# Ethernet.net
KiCad netlist of a schematic drawn in Altium Designer
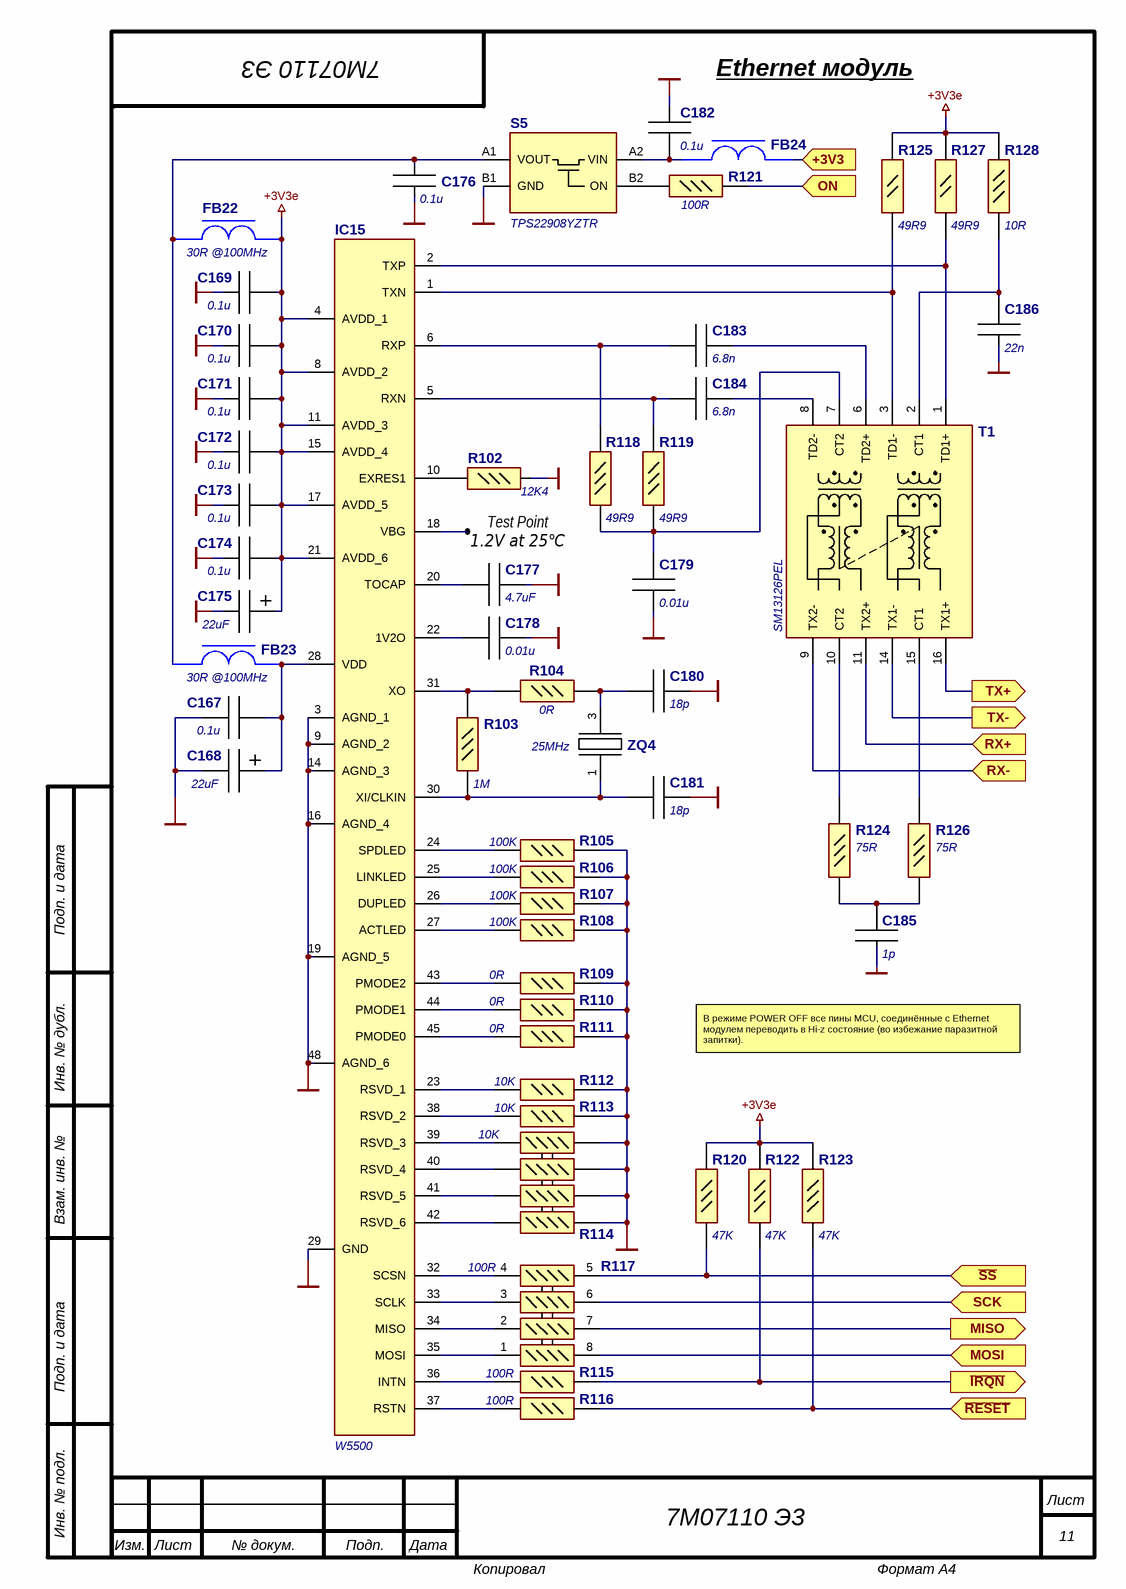
[diagram p0: Ethernet модуль.SchDoc]

(export (version "E")
  (design (tool "Eeschema 10.0.6"))
  (components
    (comp (ref "C167")
      (value "0.1u")
      (footprint ":CAP0402 100x50x50")
      (description "±10% 25V Ceramic Capacitor X7R 0402 (1005 Metric)")
      (fields
        (field (name "MANUFACTURER_PART_NUMBER") "GRM155R71E104KE14J")
        (field (name "MOUSER PART NUMBER") "81-GRM155R71E104KE4J")
      )
      (libsource (lib "Capacitors 0402") (part "GRM155R71E104KE14J"))
    )
    (comp (ref "C168")
      (value "22uF")
      (footprint ":CAP1206 C3216-18")
      (description "22µF Molded Tantalum Capacitors 6.3V 1206 (3216 Metric) 300mOhm @ 100kHz")
      (fields (field (name "MANUFACTURER_PART_NUMBER") "TPSA226K006R0300"))
      (libsource (lib "Capacitors 1206") (part "TPSA226K006R0300"))
    )
    (comp (ref "C169")
      (value "0.1u")
      (footprint ":CAP0402 100x50x50")
      (description "±10% 25V Ceramic Capacitor X7R 0402 (1005 Metric)")
      (fields
        (field (name "MANUFACTURER_PART_NUMBER") "GRM155R71E104KE14J")
        (field (name "MOUSER PART NUMBER") "81-GRM155R71E104KE4J")
      )
      (libsource (lib "Capacitors 0402") (part "GRM155R71E104KE14J"))
    )
    (comp (ref "C170")
      (value "0.1u")
      (footprint ":CAP0402 100x50x50")
      (description "±10% 25V Ceramic Capacitor X7R 0402 (1005 Metric)")
      (fields
        (field (name "MANUFACTURER_PART_NUMBER") "GRM155R71E104KE14J")
        (field (name "MOUSER PART NUMBER") "81-GRM155R71E104KE4J")
      )
      (libsource (lib "Capacitors 0402") (part "GRM155R71E104KE14J"))
    )
    (comp (ref "C171")
      (value "0.1u")
      (footprint ":CAP0402 100x50x50")
      (description "±10% 25V Ceramic Capacitor X7R 0402 (1005 Metric)")
      (fields
        (field (name "MANUFACTURER_PART_NUMBER") "GRM155R71E104KE14J")
        (field (name "MOUSER PART NUMBER") "81-GRM155R71E104KE4J")
      )
      (libsource (lib "Capacitors 0402") (part "GRM155R71E104KE14J"))
    )
    (comp (ref "C172")
      (value "0.1u")
      (footprint ":CAP0402 100x50x50")
      (description "±10% 25V Ceramic Capacitor X7R 0402 (1005 Metric)")
      (fields
        (field (name "MANUFACTURER_PART_NUMBER") "GRM155R71E104KE14J")
        (field (name "MOUSER PART NUMBER") "81-GRM155R71E104KE4J")
      )
      (libsource (lib "Capacitors 0402") (part "GRM155R71E104KE14J"))
    )
    (comp (ref "C173")
      (value "0.1u")
      (footprint ":CAP0402 100x50x50")
      (description "±10% 25V Ceramic Capacitor X7R 0402 (1005 Metric)")
      (fields
        (field (name "MANUFACTURER_PART_NUMBER") "GRM155R71E104KE14J")
        (field (name "MOUSER PART NUMBER") "81-GRM155R71E104KE4J")
      )
      (libsource (lib "Capacitors 0402") (part "GRM155R71E104KE14J"))
    )
    (comp (ref "C174")
      (value "0.1u")
      (footprint ":CAP0402 100x50x50")
      (description "±10% 25V Ceramic Capacitor X7R 0402 (1005 Metric)")
      (fields
        (field (name "MANUFACTURER_PART_NUMBER") "GRM155R71E104KE14J")
        (field (name "MOUSER PART NUMBER") "81-GRM155R71E104KE4J")
      )
      (libsource (lib "Capacitors 0402") (part "GRM155R71E104KE14J"))
    )
    (comp (ref "C175")
      (value "22uF")
      (footprint ":CAP1206 C3216-18")
      (description "22µF Molded Tantalum Capacitors 6.3V 1206 (3216 Metric) 300mOhm @ 100kHz")
      (fields (field (name "MANUFACTURER_PART_NUMBER") "TPSA226K006R0300"))
      (libsource (lib "Capacitors 1206") (part "TPSA226K006R0300"))
    )
    (comp (ref "C176")
      (value "0.1u")
      (footprint ":CAP0402 100x50x50")
      (description "±10% 25V Ceramic Capacitor X7R 0402 (1005 Metric)")
      (fields
        (field (name "MANUFACTURER_PART_NUMBER") "GRM155R71E104KE14J")
        (field (name "MOUSER PART NUMBER") "81-GRM155R71E104KE4J")
      )
      (libsource (lib "") (part "GRM155R71E104KE14J_1"))
    )
    (comp (ref "C177")
      (value "4.7uF")
      (footprint ":CAP0805 C2012X125")
      (description "CAP CER 4.7uF 25V X7R 0805")
      (fields (field (name "MANUFACTURER_PART_NUMBER") "GRM21BZ71E475KE15L"))
      (libsource (lib "Capacitors 0805") (part "GRM21BZ71E475KE15L"))
    )
    (comp (ref "C178")
      (value "0.01u")
      (footprint ":CAP0402 100x50x50")
      (description "±5% 35V Ceramic Capacitor C0G, NP0 0402 (1005 Metric)")
      (fields (field (name "MANUFACTURER_PART_NUMBER") "GRM1555CYA103JE01D"))
      (libsource (lib "Capacitors 0402") (part "GRM1555CYA103JE01D"))
    )
    (comp (ref "C179")
      (value "0.01u")
      (footprint ":CAP0402 100x50x50")
      (description "±5% 35V Ceramic Capacitor C0G, NP0 0402 (1005 Metric)")
      (fields (field (name "MANUFACTURER_PART_NUMBER") "GRM1555CYA103JE01D"))
      (libsource (lib "Capacitors 0402") (part "GRM1555CYA103JE01D"))
    )
    (comp (ref "C180")
      (value "18p")
      (footprint ":CAP0402 100x50x50")
      (description "CAP CER  50V C0G/NP0 0402")
      (fields (field (name "MANUFACTURER_PART_NUMBER") "GJM1555C1H180JB01D"))
      (libsource (lib "Capacitors 0402") (part "GJM1555C1H180JB01D"))
    )
    (comp (ref "C181")
      (value "18p")
      (footprint ":CAP0402 100x50x50")
      (description "CAP CER  50V C0G/NP0 0402")
      (fields (field (name "MANUFACTURER_PART_NUMBER") "GJM1555C1H180JB01D"))
      (libsource (lib "Capacitors 0402") (part "GJM1555C1H180JB01D"))
    )
    (comp (ref "C182")
      (value "0.1u")
      (footprint ":CAP0402 100x50x50")
      (description "±10% 25V Ceramic Capacitor X7R 0402 (1005 Metric)")
      (fields
        (field (name "MANUFACTURER_PART_NUMBER") "GRM155R71E104KE14J")
        (field (name "MOUSER PART NUMBER") "81-GRM155R71E104KE4J")
      )
      (libsource (lib "Capacitors 0402") (part "GRM155R71E104KE14J"))
    )
    (comp (ref "C183")
      (value "6.8n")
      (footprint ":CAP0402 100x50x50")
      (description "CAP CER  25V X7R 0402")
      (fields (field (name "MANUFACTURER_PART_NUMBER") "GCM155R71E682KA37D"))
      (libsource (lib "Capacitors 0402") (part "GCM155R71E682KA37D"))
    )
    (comp (ref "C184")
      (value "6.8n")
      (footprint ":CAP0402 100x50x50")
      (description "CAP CER  25V X7R 0402")
      (fields (field (name "MANUFACTURER_PART_NUMBER") "GCM155R71E682KA37D"))
      (libsource (lib "Capacitors 0402") (part "GCM155R71E682KA37D"))
    )
    (comp (ref "C185")
      (value "1p")
      (footprint ":CAP0402 100x50x50")
      (description "CAP CER  50V C0G/NP0 0402")
      (fields (field (name "MANUFACTURER_PART_NUMBER") "GJM1555C1H1R0BB01D"))
      (libsource (lib "Capacitors 0402") (part "GJM1555C1H1R0BB01D"))
    )
    (comp (ref "C186")
      (value "22n")
      (footprint ":CAP0402 100x50x50")
      (description "CAP CER  25V X7R 0402")
      (fields (field (name "MANUFACTURER_PART_NUMBER") "GCM155R71E223KA55D"))
      (libsource (lib "Capacitors 0402") (part "GCM155R71E223KA55D"))
    )
    (comp (ref "FB22")
      (value "30R @100MHz")
      (footprint ":FER BLM18SP300SN1D")
      (description "30 Ohms @ 100MHz 1 Power Line Ferrite Bead 0603 (1608 Metric) 6A 8mOhm")
      (fields
        (field (name "MANUFACTURER_PART_NUMBER") "BLM18SP300SN1D")
        (field (name "MOUSER PART NUMBER") "81-BLM18SP300SN1D")
      )
      (libsource (lib "Ferrite Bead") (part "BLM18SP300SN1D"))
    )
    (comp (ref "FB23")
      (value "30R @100MHz")
      (footprint ":FER BLM18SP300SN1D")
      (description "30 Ohms @ 100MHz 1 Power Line Ferrite Bead 0603 (1608 Metric) 6A 8mOhm")
      (fields
        (field (name "MANUFACTURER_PART_NUMBER") "BLM18SP300SN1D")
        (field (name "MOUSER PART NUMBER") "81-BLM18SP300SN1D")
      )
      (libsource (lib "Ferrite Bead") (part "BLM18SP300SN1D"))
    )
    (comp (ref "FB24")
      (value "30R @100MHz")
      (footprint ":FER BLM18SP300SN1D")
      (description "30 Ohms @ 100MHz 1 Power Line Ferrite Bead 0603 (1608 Metric) 6A 8mOhm")
      (fields
        (field (name "MANUFACTURER_PART_NUMBER") "BLM18SP300SN1D")
        (field (name "MOUSER PART NUMBER") "81-BLM18SP300SN1D")
      )
      (libsource (lib "Ferrite Bead") (part "BLM18SP300SN1D"))
    )
    (comp (ref "IC15")
      (value "W5500")
      (footprint ":QFP48 P900X900X160-48N")
      (description "Ethernet ICs 3in1 Enet Controller TCP/IP +MAC+PHY")
      (libsource (lib "Digital ICs") (part "W5500"))
    )
    (comp (ref "R102")
      (value "RC0402FR-07")
      (footprint ":RES0402")
      (fields (field (name "MANUFACTURER_PART_NUMBER (PART 2: VALUE)") "12K4"))
      (libsource (lib "Resistors 0402") (part "RC0402FR-07"))
    )
    (comp (ref "R103")
      (value "RC0402FR-07")
      (footprint ":RES0402")
      (fields (field (name "MANUFACTURER_PART_NUMBER (PART 2: VALUE)") "1M"))
      (libsource (lib "") (part "RC0402FR-07_1"))
    )
    (comp (ref "R104")
      (value "RC0402FR-07")
      (footprint ":RES0402")
      (fields (field (name "MANUFACTURER_PART_NUMBER (PART 2: VALUE)") "0R"))
      (libsource (lib "Resistors 0402") (part "RC0402FR-07"))
    )
    (comp (ref "R105")
      (value "RC0402FR-07")
      (footprint ":RES0402")
      (fields (field (name "MANUFACTURER_PART_NUMBER (PART 2: VALUE)") "100K"))
      (libsource (lib "Resistors 0402") (part "RC0402FR-07"))
    )
    (comp (ref "R106")
      (value "RC0402FR-07")
      (footprint ":RES0402")
      (fields (field (name "MANUFACTURER_PART_NUMBER (PART 2: VALUE)") "100K"))
      (libsource (lib "Resistors 0402") (part "RC0402FR-07"))
    )
    (comp (ref "R107")
      (value "RC0402FR-07")
      (footprint ":RES0402")
      (fields (field (name "MANUFACTURER_PART_NUMBER (PART 2: VALUE)") "100K"))
      (libsource (lib "Resistors 0402") (part "RC0402FR-07"))
    )
    (comp (ref "R108")
      (value "RC0402FR-07")
      (footprint ":RES0402")
      (fields (field (name "MANUFACTURER_PART_NUMBER (PART 2: VALUE)") "100K"))
      (libsource (lib "Resistors 0402") (part "RC0402FR-07"))
    )
    (comp (ref "R109")
      (value "RC0402FR-07")
      (footprint ":RES0402")
      (fields (field (name "MANUFACTURER_PART_NUMBER (PART 2: VALUE)") "0R"))
      (libsource (lib "Resistors 0402") (part "RC0402FR-07"))
    )
    (comp (ref "R110")
      (value "RC0402FR-07")
      (footprint ":RES0402")
      (fields (field (name "MANUFACTURER_PART_NUMBER (PART 2: VALUE)") "0R"))
      (libsource (lib "Resistors 0402") (part "RC0402FR-07"))
    )
    (comp (ref "R111")
      (value "RC0402FR-07")
      (footprint ":RES0402")
      (fields (field (name "MANUFACTURER_PART_NUMBER (PART 2: VALUE)") "0R"))
      (libsource (lib "Resistors 0402") (part "RC0402FR-07"))
    )
    (comp (ref "R112")
      (value "RC0402FR-07")
      (footprint ":RES0402")
      (fields (field (name "MANUFACTURER_PART_NUMBER (PART 2: VALUE)") "10K"))
      (libsource (lib "") (part "RC0402FR-07_2"))
    )
    (comp (ref "R113")
      (value "RC0402FR-07")
      (footprint ":RES0402")
      (fields (field (name "MANUFACTURER_PART_NUMBER (PART 2: VALUE)") "10K"))
      (libsource (lib "") (part "RC0402FR-07_2"))
    )
    (comp (ref "R114")
      (value "10K")
      (footprint ":RES0402x4")
      (fields (field (name "MANUFACTURER_PART_NUMBER") "EXB-N8V103JX"))
      (libsource (lib "Resistors Arrays") (part "EXB-N8V103JX"))
    )
    (comp (ref "R115")
      (value "RC0402FR-07")
      (footprint ":RES0402")
      (fields (field (name "MANUFACTURER_PART_NUMBER (PART 2: VALUE)") "100R"))
      (libsource (lib "Resistors 0402") (part "RC0402FR-07"))
    )
    (comp (ref "R116")
      (value "RC0402FR-07")
      (footprint ":RES0402")
      (fields (field (name "MANUFACTURER_PART_NUMBER (PART 2: VALUE)") "100R"))
      (libsource (lib "Resistors 0402") (part "RC0402FR-07"))
    )
    (comp (ref "R117")
      (value "100R")
      (footprint ":RES0402x4")
      (fields
        (field (name "MANUFACTURER_PART_NUMBER") "EXB-N8V101JX")
        (field (name "MOUSER PART NUMBER") "667-EXB-N8V101JX")
      )
      (libsource (lib "Resistors Arrays") (part "EXB-N8V101JX"))
    )
    (comp (ref "R118")
      (value "RC0402FR-07")
      (footprint ":RES0402")
      (fields (field (name "MANUFACTURER_PART_NUMBER (PART 2: VALUE)") "49R9"))
      (libsource (lib "") (part "RC0402FR-07_1"))
    )
    (comp (ref "R119")
      (value "RC0402FR-07")
      (footprint ":RES0402")
      (fields (field (name "MANUFACTURER_PART_NUMBER (PART 2: VALUE)") "49R9"))
      (libsource (lib "") (part "RC0402FR-07_1"))
    )
    (comp (ref "R120")
      (value "RC0402FR-07")
      (footprint ":RES0402")
      (fields (field (name "MANUFACTURER_PART_NUMBER (PART 2: VALUE)") "47K"))
      (libsource (lib "") (part "RC0402FR-07_1"))
    )
    (comp (ref "R121")
      (value "RC0402FR-07")
      (footprint ":RES0402")
      (fields (field (name "MANUFACTURER_PART_NUMBER (PART 2: VALUE)") "100R"))
      (libsource (lib "Resistors 0402") (part "RC0402FR-07"))
    )
    (comp (ref "R122")
      (value "RC0402FR-07")
      (footprint ":RES0402")
      (fields (field (name "MANUFACTURER_PART_NUMBER (PART 2: VALUE)") "47K"))
      (libsource (lib "") (part "RC0402FR-07_1"))
    )
    (comp (ref "R123")
      (value "RC0402FR-07")
      (footprint ":RES0402")
      (fields (field (name "MANUFACTURER_PART_NUMBER (PART 2: VALUE)") "47K"))
      (libsource (lib "") (part "RC0402FR-07_1"))
    )
    (comp (ref "R124")
      (value "RC0402FR-07")
      (footprint ":RES0402")
      (fields (field (name "MANUFACTURER_PART_NUMBER (PART 2: VALUE)") "75R"))
      (libsource (lib "") (part "RC0402FR-07_3"))
    )
    (comp (ref "R125")
      (value "49R9")
      (footprint ":RES0805")
      (description "49.9 Ohms ±1% 0.125W, 1/8W Chip Resistor 0805 (2012 Metric) Automotive AEC-Q200 Thick Film")
      (fields
        (field (name "MANUFACTURER_PART_NUMBER") "ERJ-6ENF49R9V")
        (field (name "MOUSER PART NUMBER") "667-ERJ-6ENF49R9V")
      )
      (libsource (lib "Resistors 0805") (part "ERJ-6ENF49R9V"))
    )
    (comp (ref "R126")
      (value "RC0402FR-07")
      (footprint ":RES0402")
      (fields (field (name "MANUFACTURER_PART_NUMBER (PART 2: VALUE)") "75R"))
      (libsource (lib "") (part "RC0402FR-07_3"))
    )
    (comp (ref "R127")
      (value "49R9")
      (footprint ":RES0805")
      (description "49.9 Ohms ±1% 0.125W, 1/8W Chip Resistor 0805 (2012 Metric) Automotive AEC-Q200 Thick Film")
      (fields
        (field (name "MANUFACTURER_PART_NUMBER") "ERJ-6ENF49R9V")
        (field (name "MOUSER PART NUMBER") "667-ERJ-6ENF49R9V")
      )
      (libsource (lib "Resistors 0805") (part "ERJ-6ENF49R9V"))
    )
    (comp (ref "R128")
      (value "RC0402FR-07")
      (footprint ":RES0402")
      (fields (field (name "MANUFACTURER_PART_NUMBER (PART 2: VALUE)") "10R"))
      (libsource (lib "") (part "RC0402FR-07_1"))
    )
    (comp (ref "S5")
      (value "TPS22908YZTR")
      (footprint ":BGA4 P90X90X50")
      (description "SPST Switch 3.6-V, 1-A, 28-mΩ")
      (fields (field (name "MOUSER PART NUMBER") "595-TPS22908YZTR"))
      (libsource (lib "Switching and Relays") (part "TPS22908YZTR"))
    )
    (comp (ref "T1")
      (value "SM13126PEL")
      (footprint ":TRAN SM13126PEL")
      (description "Transformers LAN 10/100 BASE-T")
      (fields (field (name "MOUSER PART NUMBER") "652-SM13126PEL"))
      (libsource (lib "Transformers") (part "SM13126PEL"))
    )
    (comp (ref "X3")
      (value "Big Circle Pad")
      (description "Большая круглая контактная площадка")
      (libsource (lib "Connectors") (part "Big Circle Pad"))
    )
    (comp (ref "ZQ4")
      (value "25MHz")
      (footprint ":RESO SXT22418FB48-25.000MT")
      (description "CRYSTAL 25MHz\r\n±10ppm Crystal 18pF 4-SMD\r\nESR: 80 Ohms")
      (fields (field (name "MANUFACTURER_PART_NUMBER") "SXT22418FB48-25.000MT"))
      (libsource (lib "Crystal and TXCO") (part "SXT22418FB48-25.000MT"))
    )
  )
  (nets
    (net (code "1") (name "+3V3e") (class "Default")
      (node (ref "C169") (pin "2") (pinfunction "2_2") (pintype "passive"))
      (node (ref "C170") (pin "2") (pinfunction "2_2") (pintype "passive"))
      (node (ref "C171") (pin "2") (pinfunction "2_2") (pintype "passive"))
      (node (ref "C172") (pin "2") (pinfunction "2_2") (pintype "passive"))
      (node (ref "C173") (pin "2") (pinfunction "2_2") (pintype "passive"))
      (node (ref "C174") (pin "2") (pinfunction "2_2") (pintype "passive"))
      (node (ref "C175") (pin "1") (pinfunction "+_1") (pintype "passive"))
      (node (ref "FB22") (pin "2") (pinfunction "2_2") (pintype "passive"))
      (node (ref "IC15") (pin "11") (pinfunction "AVDD_3_11") (pintype "passive"))
      (node (ref "IC15") (pin "15") (pinfunction "AVDD_4_15") (pintype "passive"))
      (node (ref "IC15") (pin "17") (pinfunction "AVDD_5_17") (pintype "passive"))
      (node (ref "IC15") (pin "21") (pinfunction "AVDD_6_21") (pintype "passive"))
      (node (ref "IC15") (pin "4") (pinfunction "AVDD_1_4") (pintype "passive"))
      (node (ref "IC15") (pin "8") (pinfunction "AVDD_2_8") (pintype "passive"))
      (node (ref "R120") (pin "2") (pinfunction "2_2") (pintype "passive"))
      (node (ref "R122") (pin "2") (pinfunction "2_2") (pintype "passive"))
      (node (ref "R123") (pin "2") (pinfunction "2_2") (pintype "passive"))
      (node (ref "R125") (pin "2") (pinfunction "2_2") (pintype "passive"))
      (node (ref "R127") (pin "2") (pinfunction "2_2") (pintype "passive"))
      (node (ref "R128") (pin "2") (pinfunction "2_2") (pintype "passive"))
    )
    (net (code "2") (name "/+3V3") (class "Default")
      (node (ref "FB24") (pin "2") (pinfunction "2_2") (pintype "passive"))
    )
    (net (code "3") (name "/MISO") (class "Default")
      (node (ref "R117") (pin "7") (pinfunction "7_7") (pintype "passive"))
    )
    (net (code "4") (name "/MOSI") (class "Default")
      (node (ref "R117") (pin "8") (pinfunction "8_8") (pintype "passive"))
    )
    (net (code "5") (name "/ON") (class "Default")
      (node (ref "R121") (pin "2") (pinfunction "2_2") (pintype "passive"))
    )
    (net (code "6") (name "/RX+") (class "Default")
      (node (ref "T1") (pin "11") (pinfunction "TX2+_11") (pintype "passive"))
    )
    (net (code "7") (name "/RX-") (class "Default")
      (node (ref "T1") (pin "9") (pinfunction "TX2-_9") (pintype "passive"))
    )
    (net (code "8") (name "/SCK") (class "Default")
      (node (ref "R117") (pin "6") (pinfunction "6_6") (pintype "passive"))
    )
    (net (code "9") (name "/TX+") (class "Default")
      (node (ref "T1") (pin "16") (pinfunction "TX1+_16") (pintype "passive"))
    )
    (net (code "10") (name "/TX-") (class "Default")
      (node (ref "T1") (pin "14") (pinfunction "TX1-_14") (pintype "passive"))
    )
    (net (code "11") (name "/~{IRQN}") (class "Default")
      (node (ref "R115") (pin "2") (pinfunction "2_2") (pintype "passive"))
      (node (ref "R122") (pin "1") (pinfunction "1_1") (pintype "passive"))
    )
    (net (code "12") (name "/~{RESET}") (class "Default")
      (node (ref "R116") (pin "2") (pinfunction "2_2") (pintype "passive"))
      (node (ref "R123") (pin "1") (pinfunction "1_1") (pintype "passive"))
    )
    (net (code "13") (name "/~{SS}") (class "Default")
      (node (ref "R117") (pin "5") (pinfunction "5_5") (pintype "passive"))
      (node (ref "R120") (pin "1") (pinfunction "1_1") (pintype "passive"))
    )
    (net (code "14") (name "GND") (class "Default")
      (node (ref "C167") (pin "1") (pinfunction "1_1") (pintype "passive"))
      (node (ref "C168") (pin "2") (pinfunction "2_2") (pintype "passive"))
      (node (ref "C169") (pin "1") (pinfunction "1_1") (pintype "passive"))
      (node (ref "C170") (pin "1") (pinfunction "1_1") (pintype "passive"))
      (node (ref "C171") (pin "1") (pinfunction "1_1") (pintype "passive"))
      (node (ref "C172") (pin "1") (pinfunction "1_1") (pintype "passive"))
      (node (ref "C173") (pin "1") (pinfunction "1_1") (pintype "passive"))
      (node (ref "C174") (pin "1") (pinfunction "1_1") (pintype "passive"))
      (node (ref "C175") (pin "2") (pinfunction "2_2") (pintype "passive"))
      (node (ref "C176") (pin "2") (pinfunction "2_2") (pintype "passive"))
      (node (ref "C177") (pin "2") (pinfunction "2_2") (pintype "passive"))
      (node (ref "C178") (pin "2") (pinfunction "2_2") (pintype "passive"))
      (node (ref "C179") (pin "1") (pinfunction "1_1") (pintype "passive"))
      (node (ref "C180") (pin "2") (pinfunction "2_2") (pintype "passive"))
      (node (ref "C181") (pin "2") (pinfunction "2_2") (pintype "passive"))
      (node (ref "C182") (pin "2") (pinfunction "2_2") (pintype "passive"))
      (node (ref "C185") (pin "2") (pinfunction "2_2") (pintype "passive"))
      (node (ref "C186") (pin "1") (pinfunction "1_1") (pintype "passive"))
      (node (ref "IC15") (pin "14") (pinfunction "AGND_3_14") (pintype "passive"))
      (node (ref "IC15") (pin "16") (pinfunction "AGND_4_16") (pintype "passive"))
      (node (ref "IC15") (pin "19") (pinfunction "AGND_5_19") (pintype "passive"))
      (node (ref "IC15") (pin "29") (pinfunction "GND_29") (pintype "passive"))
      (node (ref "IC15") (pin "3") (pinfunction "AGND_1_3") (pintype "passive"))
      (node (ref "IC15") (pin "48") (pinfunction "AGND_6_48") (pintype "passive"))
      (node (ref "IC15") (pin "9") (pinfunction "AGND_2_9") (pintype "passive"))
      (node (ref "R102") (pin "2") (pinfunction "2_2") (pintype "passive"))
      (node (ref "R105") (pin "2") (pinfunction "2_2") (pintype "passive"))
      (node (ref "R106") (pin "2") (pinfunction "2_2") (pintype "passive"))
      (node (ref "R107") (pin "2") (pinfunction "2_2") (pintype "passive"))
      (node (ref "R108") (pin "2") (pinfunction "2_2") (pintype "passive"))
      (node (ref "R109") (pin "2") (pinfunction "2_2") (pintype "passive"))
      (node (ref "R110") (pin "2") (pinfunction "2_2") (pintype "passive"))
      (node (ref "R111") (pin "2") (pinfunction "2_2") (pintype "passive"))
      (node (ref "R112") (pin "1") (pinfunction "1_1") (pintype "passive"))
      (node (ref "R113") (pin "1") (pinfunction "1_1") (pintype "passive"))
      (node (ref "R114") (pin "5") (pinfunction "5_5") (pintype "passive"))
      (node (ref "R114") (pin "6") (pinfunction "6_6") (pintype "passive"))
      (node (ref "R114") (pin "7") (pinfunction "7_7") (pintype "passive"))
      (node (ref "R114") (pin "8") (pinfunction "8_8") (pintype "passive"))
      (node (ref "S5") (pin "B1") (pinfunction "GND_B1") (pintype "passive"))
    )
    (net (code "15") (name "Net-(C168-+)") (class "Default")
      (node (ref "C167") (pin "2") (pinfunction "2_2") (pintype "passive"))
      (node (ref "C168") (pin "1") (pinfunction "+_1") (pintype "passive"))
      (node (ref "FB23") (pin "2") (pinfunction "2_2") (pintype "passive"))
      (node (ref "IC15") (pin "28") (pinfunction "VDD_28") (pintype "passive"))
    )
    (net (code "16") (name "Net-(C179-Pad2)") (class "Default")
      (node (ref "C179") (pin "2") (pinfunction "2_2") (pintype "passive"))
      (node (ref "R118") (pin "1") (pinfunction "1_1") (pintype "passive"))
      (node (ref "R119") (pin "1") (pinfunction "1_1") (pintype "passive"))
      (node (ref "T1") (pin "7") (pinfunction "CT2_7") (pintype "passive"))
    )
    (net (code "17") (name "Net-(C180-Pad1)") (class "Default")
      (node (ref "C180") (pin "1") (pinfunction "1_1") (pintype "passive"))
      (node (ref "R104") (pin "2") (pinfunction "2_2") (pintype "passive"))
      (node (ref "ZQ4") (pin "3") (pinfunction "3_3") (pintype "passive"))
    )
    (net (code "18") (name "Net-(C185-Pad1)") (class "Default")
      (node (ref "C185") (pin "1") (pinfunction "1_1") (pintype "passive"))
      (node (ref "R124") (pin "2") (pinfunction "2_2") (pintype "passive"))
      (node (ref "R126") (pin "2") (pinfunction "2_2") (pintype "passive"))
    )
    (net (code "19") (name "Net-(C186-Pad2)") (class "Default")
      (node (ref "C186") (pin "2") (pinfunction "2_2") (pintype "passive"))
      (node (ref "R128") (pin "1") (pinfunction "1_1") (pintype "passive"))
      (node (ref "T1") (pin "2") (pinfunction "CT1_2") (pintype "passive"))
    )
    (net (code "20") (name "Net-(IC15-1V2O)") (class "Default")
      (node (ref "C178") (pin "1") (pinfunction "1_1") (pintype "passive"))
      (node (ref "IC15") (pin "22") (pinfunction "1V2O_22") (pintype "passive"))
    )
    (net (code "21") (name "Net-(IC15-ACTLED)") (class "Default")
      (node (ref "IC15") (pin "27") (pinfunction "ACTLED_27") (pintype "passive"))
      (node (ref "R108") (pin "1") (pinfunction "1_1") (pintype "passive"))
    )
    (net (code "22") (name "Net-(IC15-DUPLED)") (class "Default")
      (node (ref "IC15") (pin "26") (pinfunction "DUPLED_26") (pintype "passive"))
      (node (ref "R107") (pin "1") (pinfunction "1_1") (pintype "passive"))
    )
    (net (code "23") (name "Net-(IC15-EXRES1)") (class "Default")
      (node (ref "IC15") (pin "10") (pinfunction "EXRES1_10") (pintype "passive"))
      (node (ref "R102") (pin "1") (pinfunction "1_1") (pintype "passive"))
    )
    (net (code "24") (name "Net-(IC15-INTN)") (class "Default")
      (node (ref "IC15") (pin "36") (pinfunction "INTN_36") (pintype "passive"))
      (node (ref "R115") (pin "1") (pinfunction "1_1") (pintype "passive"))
    )
    (net (code "25") (name "Net-(IC15-LINKLED)") (class "Default")
      (node (ref "IC15") (pin "25") (pinfunction "LINKLED_25") (pintype "passive"))
      (node (ref "R106") (pin "1") (pinfunction "1_1") (pintype "passive"))
    )
    (net (code "26") (name "Net-(IC15-MISO)") (class "Default")
      (node (ref "IC15") (pin "34") (pinfunction "MISO_34") (pintype "passive"))
      (node (ref "R117") (pin "2") (pinfunction "2_2") (pintype "passive"))
    )
    (net (code "27") (name "Net-(IC15-MOSI)") (class "Default")
      (node (ref "IC15") (pin "35") (pinfunction "MOSI_35") (pintype "passive"))
      (node (ref "R117") (pin "1") (pinfunction "1_1") (pintype "passive"))
    )
    (net (code "28") (name "Net-(IC15-PMODE0)") (class "Default")
      (node (ref "IC15") (pin "45") (pinfunction "PMODE0_45") (pintype "passive"))
      (node (ref "R111") (pin "1") (pinfunction "1_1") (pintype "passive"))
    )
    (net (code "29") (name "Net-(IC15-PMODE1)") (class "Default")
      (node (ref "IC15") (pin "44") (pinfunction "PMODE1_44") (pintype "passive"))
      (node (ref "R110") (pin "1") (pinfunction "1_1") (pintype "passive"))
    )
    (net (code "30") (name "Net-(IC15-PMODE2)") (class "Default")
      (node (ref "IC15") (pin "43") (pinfunction "PMODE2_43") (pintype "passive"))
      (node (ref "R109") (pin "1") (pinfunction "1_1") (pintype "passive"))
    )
    (net (code "31") (name "Net-(IC15-RSTN)") (class "Default")
      (node (ref "IC15") (pin "37") (pinfunction "RSTN_37") (pintype "passive"))
      (node (ref "R116") (pin "1") (pinfunction "1_1") (pintype "passive"))
    )
    (net (code "32") (name "Net-(IC15-RSVD_1)") (class "Default")
      (node (ref "IC15") (pin "23") (pinfunction "RSVD_1_23") (pintype "passive"))
      (node (ref "R112") (pin "2") (pinfunction "2_2") (pintype "passive"))
    )
    (net (code "33") (name "Net-(IC15-RSVD_2)") (class "Default")
      (node (ref "IC15") (pin "38") (pinfunction "RSVD_2_38") (pintype "passive"))
      (node (ref "R113") (pin "2") (pinfunction "2_2") (pintype "passive"))
    )
    (net (code "34") (name "Net-(IC15-RSVD_3)") (class "Default")
      (node (ref "IC15") (pin "39") (pinfunction "RSVD_3_39") (pintype "passive"))
      (node (ref "R114") (pin "4") (pinfunction "4_4") (pintype "passive"))
    )
    (net (code "35") (name "Net-(IC15-RSVD_4)") (class "Default")
      (node (ref "IC15") (pin "40") (pinfunction "RSVD_4_40") (pintype "passive"))
      (node (ref "R114") (pin "3") (pinfunction "3_3") (pintype "passive"))
    )
    (net (code "36") (name "Net-(IC15-RSVD_5)") (class "Default")
      (node (ref "IC15") (pin "41") (pinfunction "RSVD_5_41") (pintype "passive"))
      (node (ref "R114") (pin "2") (pinfunction "2_2") (pintype "passive"))
    )
    (net (code "37") (name "Net-(IC15-RSVD_6)") (class "Default")
      (node (ref "IC15") (pin "42") (pinfunction "RSVD_6_42") (pintype "passive"))
      (node (ref "R114") (pin "1") (pinfunction "1_1") (pintype "passive"))
    )
    (net (code "38") (name "Net-(IC15-RXN)") (class "Default")
      (node (ref "C184") (pin "1") (pinfunction "1_1") (pintype "passive"))
      (node (ref "IC15") (pin "5") (pinfunction "RXN_5") (pintype "passive"))
      (node (ref "R119") (pin "2") (pinfunction "2_2") (pintype "passive"))
    )
    (net (code "39") (name "Net-(IC15-RXP)") (class "Default")
      (node (ref "C183") (pin "1") (pinfunction "1_1") (pintype "passive"))
      (node (ref "IC15") (pin "6") (pinfunction "RXP_6") (pintype "passive"))
      (node (ref "R118") (pin "2") (pinfunction "2_2") (pintype "passive"))
    )
    (net (code "40") (name "Net-(IC15-SCLK)") (class "Default")
      (node (ref "IC15") (pin "33") (pinfunction "SCLK_33") (pintype "passive"))
      (node (ref "R117") (pin "3") (pinfunction "3_3") (pintype "passive"))
    )
    (net (code "41") (name "Net-(IC15-SCSN)") (class "Default")
      (node (ref "IC15") (pin "32") (pinfunction "SCSN_32") (pintype "passive"))
      (node (ref "R117") (pin "4") (pinfunction "4_4") (pintype "passive"))
    )
    (net (code "42") (name "Net-(IC15-SPDLED)") (class "Default")
      (node (ref "IC15") (pin "24") (pinfunction "SPDLED_24") (pintype "passive"))
      (node (ref "R105") (pin "1") (pinfunction "1_1") (pintype "passive"))
    )
    (net (code "43") (name "Net-(IC15-TOCAP)") (class "Default")
      (node (ref "C177") (pin "1") (pinfunction "1_1") (pintype "passive"))
      (node (ref "IC15") (pin "20") (pinfunction "TOCAP_20") (pintype "passive"))
    )
    (net (code "44") (name "Net-(IC15-TXN)") (class "Default")
      (node (ref "IC15") (pin "1") (pinfunction "TXN_1") (pintype "passive"))
      (node (ref "R125") (pin "1") (pinfunction "1_1") (pintype "passive"))
      (node (ref "T1") (pin "3") (pinfunction "TD1-_3") (pintype "passive"))
    )
    (net (code "45") (name "Net-(IC15-TXP)") (class "Default")
      (node (ref "IC15") (pin "2") (pinfunction "TXP_2") (pintype "passive"))
      (node (ref "R127") (pin "1") (pinfunction "1_1") (pintype "passive"))
      (node (ref "T1") (pin "1") (pinfunction "TD1+_1") (pintype "passive"))
    )
    (net (code "46") (name "Net-(IC15-VBG)") (class "Default")
      (node (ref "IC15") (pin "18") (pinfunction "VBG_18") (pintype "passive"))
      (node (ref "X3") (pin "1") (pinfunction "1_1") (pintype "passive"))
    )
    (net (code "47") (name "Net-(IC15-XI{slash}CLKIN)") (class "Default")
      (node (ref "C181") (pin "1") (pinfunction "1_1") (pintype "passive"))
      (node (ref "IC15") (pin "30") (pinfunction "XI/CLKIN_30") (pintype "passive"))
      (node (ref "R103") (pin "1") (pinfunction "1_1") (pintype "passive"))
      (node (ref "ZQ4") (pin "1") (pinfunction "1_1") (pintype "passive"))
    )
    (net (code "48") (name "Net-(IC15-XO)") (class "Default")
      (node (ref "IC15") (pin "31") (pinfunction "XO_31") (pintype "passive"))
      (node (ref "R103") (pin "2") (pinfunction "2_2") (pintype "passive"))
      (node (ref "R104") (pin "1") (pinfunction "1_1") (pintype "passive"))
    )
    (net (code "49") (name "Net-(R124-Pad1)") (class "Default")
      (node (ref "R124") (pin "1") (pinfunction "1_1") (pintype "passive"))
      (node (ref "T1") (pin "10") (pinfunction "CT2_10") (pintype "passive"))
    )
    (net (code "50") (name "Net-(R126-Pad1)") (class "Default")
      (node (ref "R126") (pin "1") (pinfunction "1_1") (pintype "passive"))
      (node (ref "T1") (pin "15") (pinfunction "CT1_15") (pintype "passive"))
    )
    (net (code "51") (name "Net-(S5-ON)") (class "Default")
      (node (ref "R121") (pin "1") (pinfunction "1_1") (pintype "passive"))
      (node (ref "S5") (pin "B2") (pinfunction "ON_B2") (pintype "passive"))
    )
    (net (code "52") (name "Net-(S5-VIN)") (class "Default")
      (node (ref "C182") (pin "1") (pinfunction "1_1") (pintype "passive"))
      (node (ref "FB24") (pin "1") (pinfunction "1_1") (pintype "passive"))
      (node (ref "S5") (pin "A2") (pinfunction "VIN_A2") (pintype "passive"))
    )
    (net (code "53") (name "Net-(S5-VOUT)") (class "Default")
      (node (ref "C176") (pin "1") (pinfunction "1_1") (pintype "passive"))
      (node (ref "FB22") (pin "1") (pinfunction "1_1") (pintype "passive"))
      (node (ref "FB23") (pin "1") (pinfunction "1_1") (pintype "passive"))
      (node (ref "S5") (pin "A1") (pinfunction "VOUT_A1") (pintype "passive"))
    )
    (net (code "54") (name "Net-(T1-TD2+)") (class "Default")
      (node (ref "C183") (pin "2") (pinfunction "2_2") (pintype "passive"))
      (node (ref "T1") (pin "6") (pinfunction "TD2+_6") (pintype "passive"))
    )
    (net (code "55") (name "Net-(T1-TD2-)") (class "Default")
      (node (ref "C184") (pin "2") (pinfunction "2_2") (pintype "passive"))
      (node (ref "T1") (pin "8") (pinfunction "TD2-_8") (pintype "passive"))
    )
  )
)
